# Power_and_connectors.net
KiCad netlist of a schematic drawn in Altium Designer
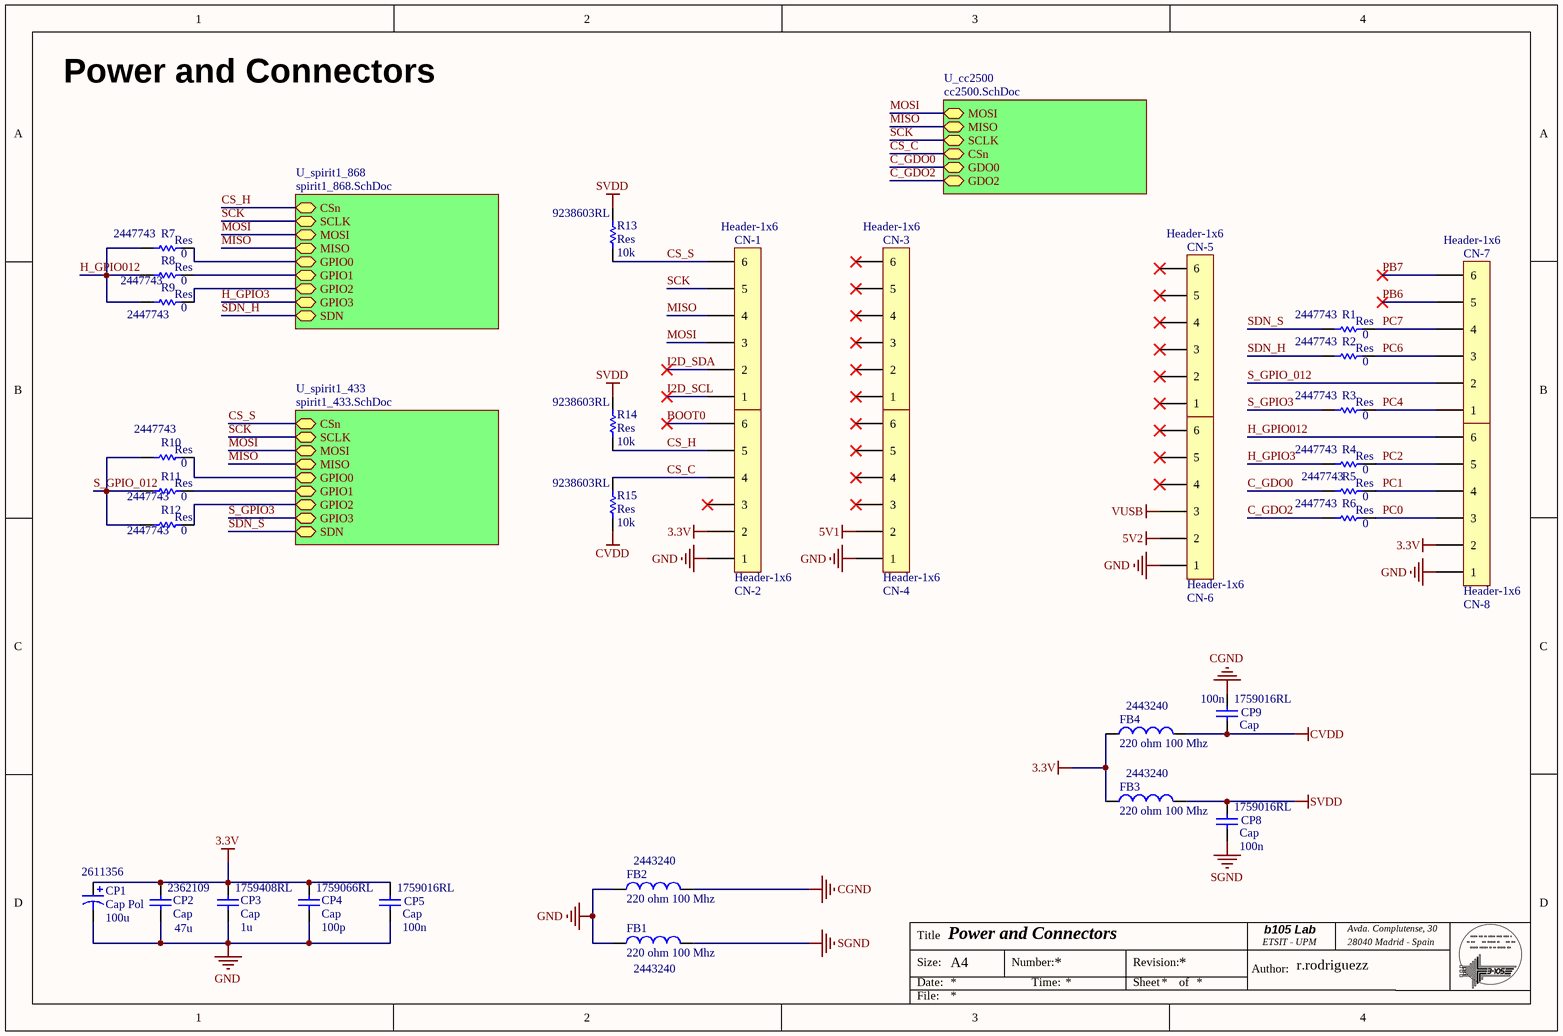
[diagram p0: Power and connectors.SchDoc]

(export (version "E")
  (design (tool "Eeschema 10.0.6"))
  (components
    (comp (ref "CN-1")
      (value "Header-1x6")
      (footprint "Header-1x6")
      (libsource (lib "B105lib") (part "Header-1x6"))
    )
    (comp (ref "CN-2")
      (value "Header-1x6")
      (footprint "Header-1x6")
      (libsource (lib "B105lib") (part "Header-1x6"))
    )
    (comp (ref "CN-3")
      (value "Header-1x6")
      (footprint "Header-1x6")
      (libsource (lib "B105lib") (part "Header-1x6"))
    )
    (comp (ref "CN-4")
      (value "Header-1x6")
      (footprint "Header-1x6")
      (libsource (lib "B105lib") (part "Header-1x6"))
    )
    (comp (ref "CN-5")
      (value "Header-1x6")
      (footprint "Header-1x6")
      (libsource (lib "B105lib") (part "Header-1x6"))
    )
    (comp (ref "CN-6")
      (value "Header-1x6")
      (footprint "Header-1x6")
      (libsource (lib "B105lib") (part "Header-1x6"))
    )
    (comp (ref "CN-7")
      (value "Header-1x6")
      (footprint "Header-1x6")
      (libsource (lib "B105lib") (part "Header-1x6"))
    )
    (comp (ref "CN-8")
      (value "Header-1x6")
      (footprint "Header-1x6")
      (libsource (lib "B105lib") (part "Header-1x6"))
    )
    (comp (ref "CP1")
      (value "Cap Pol")
      (footprint "CAP POL SMD_6.3MM")
      (fields
        (field (name "ALTIUM_VALUE") "100u")
        (field (name "SUPPLIER PART NUMBER 1") "2611356")
        (field (name "MANUFACTURER") "MULTICOMP")
        (field (name "MANUFACTURER PART NUMBER") "MCVVT016M101EA1L")
      )
      (libsource (lib "B105lib") (part "Cap Pol"))
    )
    (comp (ref "CP2")
      (value "Cap")
      (footprint "0805 CAP")
      (fields
        (field (name "ALTIUM_VALUE") "47u")
        (field (name "SUPPLIER PART NUMBER 1") "2362109")
        (field (name "MANUFACTURER") "MURATA")
        (field (name "MANUFACTURER PART NUMBER") "GRM21BR60J476ME15L")
      )
      (libsource (lib "B105lib") (part "Cap"))
    )
    (comp (ref "CP3")
      (value "Cap")
      (footprint "0603 Cap")
      (fields
        (field (name "ALTIUM_VALUE") "1u")
        (field (name "SUPPLIER PART NUMBER 1") "1759408RL")
        (field (name "MANUFACTURER") "MULTICOMP")
        (field (name "MANUFACTURER PART NUMBER") "MC0603F105Z160CT")
      )
      (libsource (lib "B105lib") (part "Cap"))
    )
    (comp (ref "CP4")
      (value "Cap")
      (footprint "0603 Cap")
      (fields
        (field (name "ALTIUM_VALUE") "100p")
        (field (name "SUPPLIER PART NUMBER 1") "1759066RL")
        (field (name "MANUFACTURER") "MULTICOMP")
        (field (name "MANUFACTURER PART NUMBER") "MC0603N101J500CT")
      )
      (libsource (lib "B105lib") (part "Cap"))
    )
    (comp (ref "CP5")
      (value "Cap")
      (footprint "0603 Cap")
      (fields
        (field (name "ALTIUM_VALUE") "100n")
        (field (name "SUPPLIER PART NUMBER 1") "1759016RL")
        (field (name "MANUFACTURER") "MULTICOMP")
        (field (name "MANUFACTURER PART NUMBER") "MC0603B104K160CT")
      )
      (libsource (lib "B105lib") (part "Cap"))
    )
    (comp (ref "CP8")
      (value "Cap")
      (footprint "0603 Cap")
      (fields
        (field (name "ALTIUM_VALUE") "100n")
        (field (name "SUPPLIER PART NUMBER 1") "1759016RL")
        (field (name "MANUFACTURER") "MULTICOMP")
        (field (name "MANUFACTURER PART NUMBER") "MC0603B104K160CT")
      )
      (libsource (lib "B105lib") (part "Cap"))
    )
    (comp (ref "CP9")
      (value "Cap")
      (footprint "0603 Cap")
      (fields
        (field (name "ALTIUM_VALUE") "100n")
        (field (name "SUPPLIER PART NUMBER 1") "1759016RL")
        (field (name "MANUFACTURER") "MULTICOMP")
        (field (name "MANUFACTURER PART NUMBER") "MC0603B104K160CT")
      )
      (libsource (lib "B105lib") (part "Cap"))
    )
    (comp (ref "FB1")
      (value "220 ohm 100 Mhz")
      (footprint "0603 Ferrite")
      (description "INDUCTOR, 0.04OHM, 3A, 0805")
      (fields
        (field (name "SUPPLIER PART NUMBER 1") "2443240")
        (field (name "MANUFACTURER") "MURATA")
        (field (name "MANUFACTURER PART NUMBER") "BLM18KG300TN1D")
      )
      (libsource (lib "B105lib") (part "Ferrita"))
    )
    (comp (ref "FB2")
      (value "220 ohm 100 Mhz")
      (footprint "0603 Ferrite")
      (description "INDUCTOR, 0.04OHM, 3A, 0805")
      (fields
        (field (name "SUPPLIER PART NUMBER 1") "2443240")
        (field (name "MANUFACTURER") "MURATA")
        (field (name "MANUFACTURER PART NUMBER") "BLM18KG300TN1D")
      )
      (libsource (lib "B105lib") (part "Ferrita"))
    )
    (comp (ref "FB3")
      (value "220 ohm 100 Mhz")
      (footprint "0603 Ferrite")
      (description "INDUCTOR, 0.04OHM, 3A, 0805")
      (fields
        (field (name "SUPPLIER PART NUMBER 1") "2443240")
        (field (name "MANUFACTURER") "MURATA")
        (field (name "MANUFACTURER PART NUMBER") "BLM18KG300TN1D")
      )
      (libsource (lib "B105lib") (part "Ferrita"))
    )
    (comp (ref "FB4")
      (value "220 ohm 100 Mhz")
      (footprint "0603 Ferrite")
      (description "INDUCTOR, 0.04OHM, 3A, 0805")
      (fields
        (field (name "SUPPLIER PART NUMBER 1") "2443240")
        (field (name "MANUFACTURER") "MURATA")
        (field (name "MANUFACTURER PART NUMBER") "BLM18KG300TN1D")
      )
      (libsource (lib "B105lib") (part "Ferrita"))
    )
    (comp (ref "R1")
      (value "Res")
      (footprint "0603 Res")
      (fields
        (field (name "ALTIUM_VALUE") "0")
        (field (name "SUPPLIER PART NUMBER 1") "2447743")
        (field (name "MANUFACTURER") "MULTICOMP")
        (field (name "MANUFACTURER PART NUMBER") "MCWR06X000 PTL")
      )
      (libsource (lib "B105lib") (part "Res"))
    )
    (comp (ref "R2")
      (value "Res")
      (footprint "0603 Res")
      (fields
        (field (name "ALTIUM_VALUE") "0")
        (field (name "SUPPLIER PART NUMBER 1") "2447743")
        (field (name "MANUFACTURER") "MULTICOMP")
        (field (name "MANUFACTURER PART NUMBER") "MCWR06X000 PTL")
      )
      (libsource (lib "B105lib") (part "Res"))
    )
    (comp (ref "R3")
      (value "Res")
      (footprint "0603 Res")
      (fields
        (field (name "ALTIUM_VALUE") "0")
        (field (name "SUPPLIER PART NUMBER 1") "2447743")
        (field (name "MANUFACTURER") "MULTICOMP")
        (field (name "MANUFACTURER PART NUMBER") "MCWR06X000 PTL")
      )
      (libsource (lib "B105lib") (part "Res"))
    )
    (comp (ref "R4")
      (value "Res")
      (footprint "0603 Res")
      (fields
        (field (name "ALTIUM_VALUE") "0")
        (field (name "SUPPLIER PART NUMBER 1") "2447743")
        (field (name "MANUFACTURER") "MULTICOMP")
        (field (name "MANUFACTURER PART NUMBER") "MCWR06X000 PTL")
      )
      (libsource (lib "B105lib") (part "Res"))
    )
    (comp (ref "R5")
      (value "Res")
      (footprint "0603 Res")
      (fields
        (field (name "ALTIUM_VALUE") "0")
        (field (name "SUPPLIER PART NUMBER 1") "2447743")
        (field (name "MANUFACTURER") "MULTICOMP")
        (field (name "MANUFACTURER PART NUMBER") "MCWR06X000 PTL")
      )
      (libsource (lib "B105lib") (part "Res"))
    )
    (comp (ref "R6")
      (value "Res")
      (footprint "0603 Res")
      (fields
        (field (name "ALTIUM_VALUE") "0")
        (field (name "SUPPLIER PART NUMBER 1") "2447743")
        (field (name "MANUFACTURER") "MULTICOMP")
        (field (name "MANUFACTURER PART NUMBER") "MCWR06X000 PTL")
      )
      (libsource (lib "B105lib") (part "Res"))
    )
    (comp (ref "R7")
      (value "Res")
      (footprint "0603 Res")
      (fields
        (field (name "ALTIUM_VALUE") "0")
        (field (name "SUPPLIER PART NUMBER 1") "2447743")
        (field (name "MANUFACTURER") "MULTICOMP")
        (field (name "MANUFACTURER PART NUMBER") "MCWR06X000 PTL")
      )
      (libsource (lib "B105lib") (part "Res"))
    )
    (comp (ref "R8")
      (value "Res")
      (footprint "0603 Res")
      (fields
        (field (name "ALTIUM_VALUE") "0")
        (field (name "SUPPLIER PART NUMBER 1") "2447743")
        (field (name "MANUFACTURER") "MULTICOMP")
        (field (name "MANUFACTURER PART NUMBER") "MCWR06X000 PTL")
      )
      (libsource (lib "B105lib") (part "Res"))
    )
    (comp (ref "R9")
      (value "Res")
      (footprint "0603 Res")
      (fields
        (field (name "ALTIUM_VALUE") "0")
        (field (name "SUPPLIER PART NUMBER 1") "2447743")
        (field (name "MANUFACTURER") "MULTICOMP")
        (field (name "MANUFACTURER PART NUMBER") "MCWR06X000 PTL")
      )
      (libsource (lib "B105lib") (part "Res"))
    )
    (comp (ref "R10")
      (value "Res")
      (footprint "0603 Res")
      (fields
        (field (name "ALTIUM_VALUE") "0")
        (field (name "SUPPLIER PART NUMBER 1") "2447743")
        (field (name "MANUFACTURER") "MULTICOMP")
        (field (name "MANUFACTURER PART NUMBER") "MCWR06X000 PTL")
      )
      (libsource (lib "B105lib") (part "Res"))
    )
    (comp (ref "R11")
      (value "Res")
      (footprint "0603 Res")
      (fields
        (field (name "ALTIUM_VALUE") "0")
        (field (name "SUPPLIER PART NUMBER 1") "2447743")
        (field (name "MANUFACTURER") "MULTICOMP")
        (field (name "MANUFACTURER PART NUMBER") "MCWR06X000 PTL")
      )
      (libsource (lib "B105lib") (part "Res"))
    )
    (comp (ref "R12")
      (value "Res")
      (footprint "0603 Res")
      (fields
        (field (name "ALTIUM_VALUE") "0")
        (field (name "SUPPLIER PART NUMBER 1") "2447743")
        (field (name "MANUFACTURER") "MULTICOMP")
        (field (name "MANUFACTURER PART NUMBER") "MCWR06X000 PTL")
      )
      (libsource (lib "B105lib") (part "Res"))
    )
    (comp (ref "R13")
      (value "Res")
      (footprint "0603 Res")
      (fields
        (field (name "ALTIUM_VALUE") "10k")
        (field (name "SUPPLIER PART NUMBER 1") "9238603RL")
        (field (name "MANUFACTURER") "YAGEO (PHYCOMP)")
        (field (name "MANUFACTURER PART NUMBER") "RC0603FR-0710KL")
      )
      (libsource (lib "B105lib") (part "Res"))
    )
    (comp (ref "R14")
      (value "Res")
      (footprint "0603 Res")
      (fields
        (field (name "ALTIUM_VALUE") "10k")
        (field (name "SUPPLIER PART NUMBER 1") "9238603RL")
        (field (name "MANUFACTURER") "YAGEO (PHYCOMP)")
        (field (name "MANUFACTURER PART NUMBER") "RC0603FR-0710KL")
      )
      (libsource (lib "B105lib") (part "Res"))
    )
    (comp (ref "R15")
      (value "Res")
      (footprint "0603 Res")
      (fields
        (field (name "ALTIUM_VALUE") "10k")
        (field (name "SUPPLIER PART NUMBER 1") "9238603RL")
        (field (name "MANUFACTURER") "YAGEO (PHYCOMP)")
        (field (name "MANUFACTURER PART NUMBER") "RC0603FR-0710KL")
      )
      (libsource (lib "B105lib") (part "Res"))
    )
  )
  (nets
    (net (code "1") (name "/BOOT0") (class "Default")
      (node (ref "CN-2") (pin "6") (pinfunction "6_6") (pintype "passive+no_connect"))
    )
    (net (code "2") (name "/CS_C") (class "Default")
      (node (ref "CN-2") (pin "4") (pinfunction "4_4") (pintype "passive"))
      (node (ref "R15") (pin "2") (pinfunction "2_2") (pintype "passive"))
    )
    (net (code "3") (name "/CS_H") (class "Default")
      (node (ref "CN-2") (pin "5") (pinfunction "5_5") (pintype "passive"))
      (node (ref "R14") (pin "1") (pinfunction "1_1") (pintype "passive"))
    )
    (net (code "4") (name "/CS_S") (class "Default")
      (node (ref "CN-1") (pin "6") (pinfunction "6_6") (pintype "passive"))
      (node (ref "R13") (pin "1") (pinfunction "1_1") (pintype "passive"))
    )
    (net (code "5") (name "/C_GDO0") (class "Default")
      (node (ref "R5") (pin "1") (pinfunction "1_1") (pintype "passive"))
    )
    (net (code "6") (name "/C_GDO2") (class "Default")
      (node (ref "R6") (pin "1") (pinfunction "1_1") (pintype "passive"))
    )
    (net (code "7") (name "/GPIO0") (class "Default")
      (node (ref "R7") (pin "2") (pinfunction "2_2") (pintype "passive"))
    )
    (net (code "8") (name "/GPIO0_1") (class "Default")
      (node (ref "R10") (pin "2") (pinfunction "2_2") (pintype "passive"))
    )
    (net (code "9") (name "/GPIO1") (class "Default")
      (node (ref "R8") (pin "2") (pinfunction "2_2") (pintype "passive"))
    )
    (net (code "10") (name "/GPIO1_1") (class "Default")
      (node (ref "R11") (pin "2") (pinfunction "2_2") (pintype "passive"))
    )
    (net (code "11") (name "/GPIO2") (class "Default")
      (node (ref "R12") (pin "2") (pinfunction "2_2") (pintype "passive"))
    )
    (net (code "12") (name "/GPIO2_1") (class "Default")
      (node (ref "R9") (pin "2") (pinfunction "2_2") (pintype "passive"))
    )
    (net (code "13") (name "/H_GPIO3") (class "Default")
      (node (ref "R4") (pin "1") (pinfunction "1_1") (pintype "passive"))
    )
    (net (code "14") (name "/H_GPIO012") (class "Default")
      (node (ref "CN-8") (pin "6") (pinfunction "6_6") (pintype "passive"))
      (node (ref "R7") (pin "1") (pinfunction "1_1") (pintype "passive"))
      (node (ref "R8") (pin "1") (pinfunction "1_1") (pintype "passive"))
      (node (ref "R9") (pin "1") (pinfunction "1_1") (pintype "passive"))
    )
    (net (code "15") (name "/I2D_SCL") (class "Default")
      (node (ref "CN-1") (pin "1") (pinfunction "1_1") (pintype "passive+no_connect"))
    )
    (net (code "16") (name "/I2D_SDA") (class "Default")
      (node (ref "CN-1") (pin "2") (pinfunction "2_2") (pintype "passive+no_connect"))
    )
    (net (code "17") (name "/MISO") (class "Default")
      (node (ref "CN-1") (pin "4") (pinfunction "4_4") (pintype "passive"))
    )
    (net (code "18") (name "/MOSI") (class "Default")
      (node (ref "CN-1") (pin "3") (pinfunction "3_3") (pintype "passive"))
    )
    (net (code "19") (name "/PB6") (class "Default")
      (node (ref "CN-7") (pin "5") (pinfunction "5_5") (pintype "passive+no_connect"))
    )
    (net (code "20") (name "/PB7") (class "Default")
      (node (ref "CN-7") (pin "6") (pinfunction "6_6") (pintype "passive+no_connect"))
    )
    (net (code "21") (name "/PC0") (class "Default")
      (node (ref "CN-8") (pin "3") (pinfunction "3_3") (pintype "passive"))
      (node (ref "R6") (pin "2") (pinfunction "2_2") (pintype "passive"))
    )
    (net (code "22") (name "/PC1") (class "Default")
      (node (ref "CN-8") (pin "4") (pinfunction "4_4") (pintype "passive"))
      (node (ref "R5") (pin "2") (pinfunction "2_2") (pintype "passive"))
    )
    (net (code "23") (name "/PC2") (class "Default")
      (node (ref "CN-8") (pin "5") (pinfunction "5_5") (pintype "passive"))
      (node (ref "R4") (pin "2") (pinfunction "2_2") (pintype "passive"))
    )
    (net (code "24") (name "/PC4") (class "Default")
      (node (ref "CN-7") (pin "1") (pinfunction "1_1") (pintype "passive"))
      (node (ref "R3") (pin "2") (pinfunction "2_2") (pintype "passive"))
    )
    (net (code "25") (name "/PC6") (class "Default")
      (node (ref "CN-7") (pin "3") (pinfunction "3_3") (pintype "passive"))
      (node (ref "R2") (pin "2") (pinfunction "2_2") (pintype "passive"))
    )
    (net (code "26") (name "/PC7") (class "Default")
      (node (ref "CN-7") (pin "4") (pinfunction "4_4") (pintype "passive"))
      (node (ref "R1") (pin "2") (pinfunction "2_2") (pintype "passive"))
    )
    (net (code "27") (name "/SCK") (class "Default")
      (node (ref "CN-1") (pin "5") (pinfunction "5_5") (pintype "passive"))
    )
    (net (code "28") (name "/SDN_H") (class "Default")
      (node (ref "R2") (pin "1") (pinfunction "1_1") (pintype "passive"))
    )
    (net (code "29") (name "/SDN_S") (class "Default")
      (node (ref "R1") (pin "1") (pinfunction "1_1") (pintype "passive"))
    )
    (net (code "30") (name "/S_GPIO3") (class "Default")
      (node (ref "R3") (pin "1") (pinfunction "1_1") (pintype "passive"))
    )
    (net (code "31") (name "/S_GPIO_012") (class "Default")
      (node (ref "CN-7") (pin "2") (pinfunction "2_2") (pintype "passive"))
      (node (ref "R10") (pin "1") (pinfunction "1_1") (pintype "passive"))
      (node (ref "R11") (pin "1") (pinfunction "1_1") (pintype "passive"))
      (node (ref "R12") (pin "1") (pinfunction "1_1") (pintype "passive"))
    )
    (net (code "32") (name "3.3V") (class "Default")
      (node (ref "CN-2") (pin "2") (pinfunction "2_2") (pintype "passive"))
      (node (ref "CN-8") (pin "2") (pinfunction "2_2") (pintype "passive"))
      (node (ref "CP1") (pin "1") (pinfunction "1_1") (pintype "passive"))
      (node (ref "CP2") (pin "2") (pinfunction "2_2") (pintype "passive"))
      (node (ref "CP3") (pin "2") (pinfunction "2_2") (pintype "passive"))
      (node (ref "CP4") (pin "2") (pinfunction "2_2") (pintype "passive"))
      (node (ref "CP5") (pin "2") (pinfunction "2_2") (pintype "passive"))
      (node (ref "FB3") (pin "1") (pinfunction "1_1") (pintype "passive"))
      (node (ref "FB4") (pin "1") (pinfunction "1_1") (pintype "passive"))
    )
    (net (code "33") (name "5V1") (class "Default")
      (node (ref "CN-4") (pin "2") (pinfunction "2_2") (pintype "passive"))
    )
    (net (code "34") (name "5V2") (class "Default")
      (node (ref "CN-6") (pin "2") (pinfunction "2_2") (pintype "passive"))
    )
    (net (code "35") (name "CGND") (class "Default")
      (node (ref "CP9") (pin "2") (pinfunction "2_2") (pintype "passive"))
      (node (ref "FB2") (pin "2") (pinfunction "2_2") (pintype "passive"))
    )
    (net (code "36") (name "CVDD") (class "Default")
      (node (ref "CP9") (pin "1") (pinfunction "1_1") (pintype "passive"))
      (node (ref "FB4") (pin "2") (pinfunction "2_2") (pintype "passive"))
      (node (ref "R15") (pin "1") (pinfunction "1_1") (pintype "passive"))
    )
    (net (code "37") (name "GND") (class "Default")
      (node (ref "CN-2") (pin "1") (pinfunction "1_1") (pintype "passive"))
      (node (ref "CN-4") (pin "1") (pinfunction "1_1") (pintype "passive"))
      (node (ref "CN-6") (pin "1") (pinfunction "1_1") (pintype "passive"))
      (node (ref "CN-8") (pin "1") (pinfunction "1_1") (pintype "passive"))
      (node (ref "CP1") (pin "2") (pinfunction "2_2") (pintype "passive"))
      (node (ref "CP2") (pin "1") (pinfunction "1_1") (pintype "passive"))
      (node (ref "CP3") (pin "1") (pinfunction "1_1") (pintype "passive"))
      (node (ref "CP4") (pin "1") (pinfunction "1_1") (pintype "passive"))
      (node (ref "CP5") (pin "1") (pinfunction "1_1") (pintype "passive"))
      (node (ref "FB1") (pin "1") (pinfunction "1_1") (pintype "passive"))
      (node (ref "FB2") (pin "1") (pinfunction "1_1") (pintype "passive"))
    )
    (net (code "38") (name "SGND") (class "Default")
      (node (ref "CP8") (pin "1") (pinfunction "1_1") (pintype "passive"))
      (node (ref "FB1") (pin "2") (pinfunction "2_2") (pintype "passive"))
    )
    (net (code "39") (name "SVDD") (class "Default")
      (node (ref "CP8") (pin "2") (pinfunction "2_2") (pintype "passive"))
      (node (ref "FB3") (pin "2") (pinfunction "2_2") (pintype "passive"))
      (node (ref "R13") (pin "2") (pinfunction "2_2") (pintype "passive"))
      (node (ref "R14") (pin "2") (pinfunction "2_2") (pintype "passive"))
    )
    (net (code "40") (name "VUSB") (class "Default")
      (node (ref "CN-6") (pin "3") (pinfunction "3_3") (pintype "passive"))
    )
    (net (code "41") (name "unconnected-(CN-2-Pad3)") (class "Default")
      (node (ref "CN-2") (pin "3") (pinfunction "3_3") (pintype "passive+no_connect"))
    )
    (net (code "42") (name "unconnected-(CN-3-Pad1)") (class "Default")
      (node (ref "CN-3") (pin "1") (pinfunction "1_1") (pintype "passive+no_connect"))
    )
    (net (code "43") (name "unconnected-(CN-3-Pad2)") (class "Default")
      (node (ref "CN-3") (pin "2") (pinfunction "2_2") (pintype "passive+no_connect"))
    )
    (net (code "44") (name "unconnected-(CN-3-Pad3)") (class "Default")
      (node (ref "CN-3") (pin "3") (pinfunction "3_3") (pintype "passive+no_connect"))
    )
    (net (code "45") (name "unconnected-(CN-3-Pad4)") (class "Default")
      (node (ref "CN-3") (pin "4") (pinfunction "4_4") (pintype "passive+no_connect"))
    )
    (net (code "46") (name "unconnected-(CN-3-Pad5)") (class "Default")
      (node (ref "CN-3") (pin "5") (pinfunction "5_5") (pintype "passive+no_connect"))
    )
    (net (code "47") (name "unconnected-(CN-3-Pad6)") (class "Default")
      (node (ref "CN-3") (pin "6") (pinfunction "6_6") (pintype "passive+no_connect"))
    )
    (net (code "48") (name "unconnected-(CN-4-Pad3)") (class "Default")
      (node (ref "CN-4") (pin "3") (pinfunction "3_3") (pintype "passive+no_connect"))
    )
    (net (code "49") (name "unconnected-(CN-4-Pad4)") (class "Default")
      (node (ref "CN-4") (pin "4") (pinfunction "4_4") (pintype "passive+no_connect"))
    )
    (net (code "50") (name "unconnected-(CN-4-Pad5)") (class "Default")
      (node (ref "CN-4") (pin "5") (pinfunction "5_5") (pintype "passive+no_connect"))
    )
    (net (code "51") (name "unconnected-(CN-4-Pad6)") (class "Default")
      (node (ref "CN-4") (pin "6") (pinfunction "6_6") (pintype "passive+no_connect"))
    )
    (net (code "52") (name "unconnected-(CN-5-Pad1)") (class "Default")
      (node (ref "CN-5") (pin "1") (pinfunction "1_1") (pintype "passive+no_connect"))
    )
    (net (code "53") (name "unconnected-(CN-5-Pad2)") (class "Default")
      (node (ref "CN-5") (pin "2") (pinfunction "2_2") (pintype "passive+no_connect"))
    )
    (net (code "54") (name "unconnected-(CN-5-Pad3)") (class "Default")
      (node (ref "CN-5") (pin "3") (pinfunction "3_3") (pintype "passive+no_connect"))
    )
    (net (code "55") (name "unconnected-(CN-5-Pad4)") (class "Default")
      (node (ref "CN-5") (pin "4") (pinfunction "4_4") (pintype "passive+no_connect"))
    )
    (net (code "56") (name "unconnected-(CN-5-Pad5)") (class "Default")
      (node (ref "CN-5") (pin "5") (pinfunction "5_5") (pintype "passive+no_connect"))
    )
    (net (code "57") (name "unconnected-(CN-5-Pad6)") (class "Default")
      (node (ref "CN-5") (pin "6") (pinfunction "6_6") (pintype "passive+no_connect"))
    )
    (net (code "58") (name "unconnected-(CN-6-Pad4)") (class "Default")
      (node (ref "CN-6") (pin "4") (pinfunction "4_4") (pintype "passive+no_connect"))
    )
    (net (code "59") (name "unconnected-(CN-6-Pad5)") (class "Default")
      (node (ref "CN-6") (pin "5") (pinfunction "5_5") (pintype "passive+no_connect"))
    )
    (net (code "60") (name "unconnected-(CN-6-Pad6)") (class "Default")
      (node (ref "CN-6") (pin "6") (pinfunction "6_6") (pintype "passive+no_connect"))
    )
  )
)
